# MB1066.net
KiCad netlist of a schematic drawn in Altium Designer
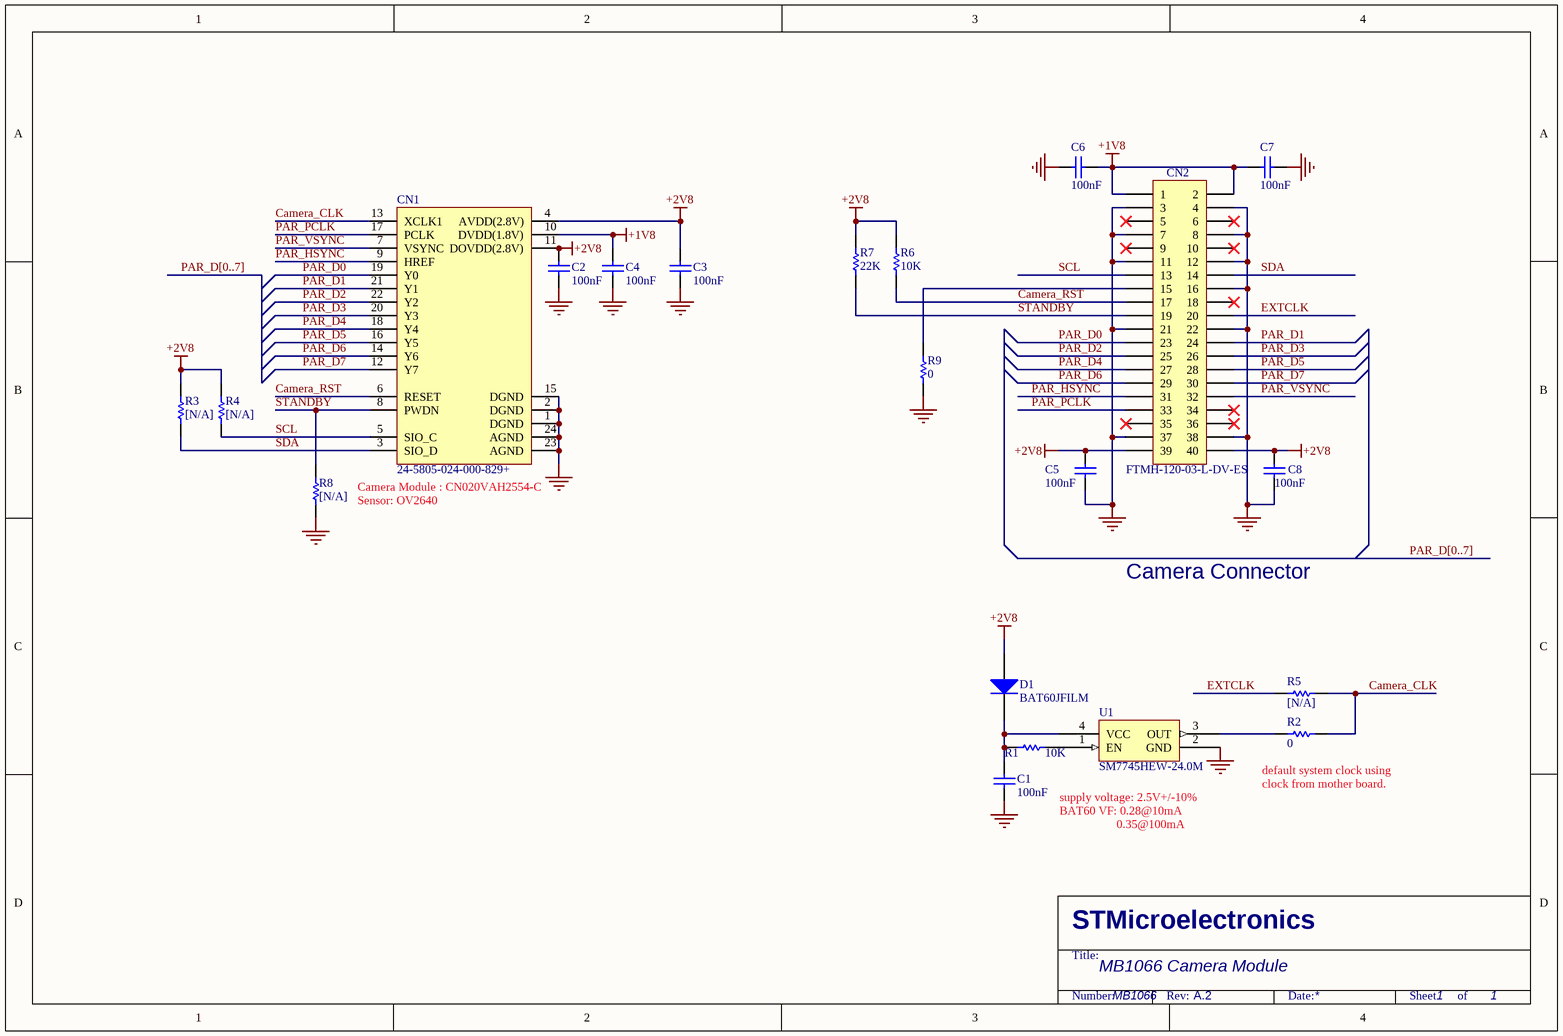
[diagram p0: MB1066.SchDoc]

(export (version "E")
  (design (tool "Eeschema 10.0.6"))
  (components
    (comp (ref "C1")
      (value "100nF")
      (footprint "0603C")
      (description "Capacitor")
      (fields (field (name "PUBLISHER") "Altium Limited"))
      (libsource (lib "Miscellaneous Devices") (part "Cap"))
    )
    (comp (ref "C2")
      (value "100nF")
      (footprint "0603C")
      (description "Capacitor")
      (fields (field (name "PUBLISHER") "Altium Limited"))
      (libsource (lib "Miscellaneous Devices") (part "Cap"))
    )
    (comp (ref "C3")
      (value "100nF")
      (footprint "0603L")
      (description "Capacitor")
      (fields (field (name "PUBLISHER") "Altium Limited"))
      (libsource (lib "Miscellaneous Devices") (part "Cap"))
    )
    (comp (ref "C4")
      (value "100nF")
      (footprint "0603C")
      (description "Capacitor")
      (fields (field (name "PUBLISHER") "Altium Limited"))
      (libsource (lib "Miscellaneous Devices") (part "Cap"))
    )
    (comp (ref "C5")
      (value "100nF")
      (footprint "0603C")
      (description "Capacitor")
      (fields (field (name "PUBLISHER") "Altium Limited"))
      (libsource (lib "Miscellaneous Devices") (part "Cap"))
    )
    (comp (ref "C6")
      (value "100nF")
      (footprint "0603C")
      (description "Capacitor")
      (fields (field (name "PUBLISHER") "Altium Limited"))
      (libsource (lib "Miscellaneous Devices") (part "Cap"))
    )
    (comp (ref "C7")
      (value "100nF")
      (footprint "0603C")
      (description "Capacitor")
      (fields (field (name "PUBLISHER") "Altium Limited"))
      (libsource (lib "Miscellaneous Devices") (part "Cap"))
    )
    (comp (ref "C8")
      (value "100nF")
      (footprint "0603C")
      (description "Capacitor")
      (fields (field (name "PUBLISHER") "Altium Limited"))
      (libsource (lib "Miscellaneous Devices") (part "Cap"))
    )
    (comp (ref "CN1")
      (value "24-5805-024-000-829+")
      (footprint "24-5805-024-000-829")
      (libsource (lib "MB786") (part "24-5805-024-000-829+"))
    )
    (comp (ref "CN2")
      (value "FTMH-120-03-L-DV-ES")
      (footprint "FTMH-120-03-L-DV-ES")
      (description "20*2Pins, 1mm_SMT, male")
      (fields (field (name "PUBLISHER") "Altium Limited"))
      (libsource (lib "Miscellaneous Connectors") (part "Header 20X2"))
    )
    (comp (ref "D1")
      (value "BAT60JFILM")
      (footprint "SOD-323")
      (description "Default Diode")
      (fields (field (name "PUBLISHER") "Altium Limited"))
      (libsource (lib "Miscellaneous Devices") (part "Diode"))
    )
    (comp (ref "R1")
      (value "10K")
      (footprint "0603R")
      (description "Resistor")
      (fields (field (name "PUBLISHER") "Altium Limited"))
      (libsource (lib "Miscellaneous Devices") (part "Res1"))
    )
    (comp (ref "R2")
      (value "0")
      (footprint "0603R")
      (description "Resistor")
      (fields (field (name "PUBLISHER") "Altium Limited"))
      (libsource (lib "Miscellaneous Devices") (part "Res1"))
    )
    (comp (ref "R3")
      (value "[N/A]")
      (footprint "0603R")
      (description "Resistor 10K")
      (fields (field (name "PUBLISHER") "Altium Limited"))
      (libsource (lib "Miscellaneous Devices") (part "Res1"))
    )
    (comp (ref "R4")
      (value "[N/A]")
      (footprint "0603R")
      (description "Resistor")
      (fields (field (name "PUBLISHER") "Altium Limited"))
      (libsource (lib "Miscellaneous Devices") (part "Res1"))
    )
    (comp (ref "R5")
      (value "[N/A]")
      (footprint "0603R")
      (description "Resistor")
      (fields (field (name "PUBLISHER") "Altium Limited"))
      (libsource (lib "Miscellaneous Devices") (part "Res1"))
    )
    (comp (ref "R6")
      (value "10K")
      (footprint "0603R")
      (description "Resistor")
      (fields (field (name "PUBLISHER") "Altium Limited"))
      (libsource (lib "Miscellaneous Devices") (part "Res1"))
    )
    (comp (ref "R7")
      (value "22K")
      (footprint "0603R")
      (description "Resistor")
      (fields (field (name "PUBLISHER") "Altium Limited"))
      (libsource (lib "Miscellaneous Devices") (part "Res1"))
    )
    (comp (ref "R8")
      (value "[N/A]")
      (footprint "0603R")
      (description "Resistor")
      (fields (field (name "PUBLISHER") "Altium Limited"))
      (libsource (lib "Miscellaneous Devices") (part "Res1"))
    )
    (comp (ref "R9")
      (value "0")
      (footprint "0603R")
      (description "Resistor")
      (fields (field (name "PUBLISHER") "Altium Limited"))
      (libsource (lib "Miscellaneous Devices") (part "Res1"))
    )
    (comp (ref "U1")
      (value "SM7745HEW-24.0M")
      (footprint "XTAL_5X7")
      (libsource (lib "MB784") (part "SM7745HEV-50.0M"))
    )
  )
  (nets
    (net (code "1") (name "+1V8") (class "Default")
      (node (ref "C4") (pin "1") (pinfunction "1_1") (pintype "passive"))
      (node (ref "C6") (pin "2") (pinfunction "2_2") (pintype "passive"))
      (node (ref "C7") (pin "1") (pinfunction "1_1") (pintype "passive"))
      (node (ref "CN1") (pin "10") (pinfunction "DVDD(1.8V)_10") (pintype "passive"))
      (node (ref "CN2") (pin "1") (pinfunction "1_1") (pintype "passive"))
      (node (ref "CN2") (pin "2") (pinfunction "2_2") (pintype "passive"))
    )
    (net (code "2") (name "+2V8") (class "Default")
      (node (ref "C2") (pin "1") (pinfunction "1_1") (pintype "passive"))
      (node (ref "C3") (pin "1") (pinfunction "1_1") (pintype "passive"))
      (node (ref "C5") (pin "1") (pinfunction "1_1") (pintype "passive"))
      (node (ref "C8") (pin "1") (pinfunction "1_1") (pintype "passive"))
      (node (ref "CN1") (pin "11") (pinfunction "DOVDD(2.8V)_11") (pintype "passive"))
      (node (ref "CN1") (pin "4") (pinfunction "AVDD(2.8V)_4") (pintype "passive"))
      (node (ref "CN2") (pin "39") (pinfunction "39_39") (pintype "passive"))
      (node (ref "CN2") (pin "40") (pinfunction "40_40") (pintype "passive"))
      (node (ref "D1") (pin "1") (pinfunction "A_1") (pintype "passive"))
      (node (ref "R3") (pin "1") (pinfunction "1_1") (pintype "passive"))
      (node (ref "R4") (pin "1") (pinfunction "1_1") (pintype "passive"))
      (node (ref "R6") (pin "1") (pinfunction "1_1") (pintype "passive"))
      (node (ref "R7") (pin "1") (pinfunction "1_1") (pintype "passive"))
    )
    (net (code "3") (name "/Camera_CLK") (class "Default")
      (node (ref "CN1") (pin "13") (pinfunction "XCLK1_13") (pintype "passive"))
      (node (ref "R2") (pin "2") (pinfunction "2_2") (pintype "passive"))
      (node (ref "R5") (pin "2") (pinfunction "2_2") (pintype "passive"))
    )
    (net (code "4") (name "/Camera_RST") (class "Default")
      (node (ref "CN1") (pin "6") (pinfunction "RESET_6") (pintype "passive"))
      (node (ref "CN2") (pin "17") (pinfunction "17_17") (pintype "passive"))
      (node (ref "R6") (pin "2") (pinfunction "2_2") (pintype "passive"))
    )
    (net (code "5") (name "/EXTCLK") (class "Default")
      (node (ref "CN2") (pin "20") (pinfunction "20_20") (pintype "passive"))
      (node (ref "R5") (pin "1") (pinfunction "1_1") (pintype "passive"))
    )
    (net (code "6") (name "/PAR_D0") (class "Default")
      (node (ref "CN1") (pin "19") (pinfunction "Y0_19") (pintype "passive"))
      (node (ref "CN2") (pin "23") (pinfunction "23_23") (pintype "passive"))
    )
    (net (code "7") (name "/PAR_D1") (class "Default")
      (node (ref "CN1") (pin "21") (pinfunction "Y1_21") (pintype "passive"))
      (node (ref "CN2") (pin "24") (pinfunction "24_24") (pintype "passive"))
    )
    (net (code "8") (name "/PAR_D2") (class "Default")
      (node (ref "CN1") (pin "22") (pinfunction "Y2_22") (pintype "passive"))
      (node (ref "CN2") (pin "25") (pinfunction "25_25") (pintype "passive"))
    )
    (net (code "9") (name "/PAR_D3") (class "Default")
      (node (ref "CN1") (pin "20") (pinfunction "Y3_20") (pintype "passive"))
      (node (ref "CN2") (pin "26") (pinfunction "26_26") (pintype "passive"))
    )
    (net (code "10") (name "/PAR_D4") (class "Default")
      (node (ref "CN1") (pin "18") (pinfunction "Y4_18") (pintype "passive"))
      (node (ref "CN2") (pin "27") (pinfunction "27_27") (pintype "passive"))
    )
    (net (code "11") (name "/PAR_D5") (class "Default")
      (node (ref "CN1") (pin "16") (pinfunction "Y5_16") (pintype "passive"))
      (node (ref "CN2") (pin "28") (pinfunction "28_28") (pintype "passive"))
    )
    (net (code "12") (name "/PAR_D6") (class "Default")
      (node (ref "CN1") (pin "14") (pinfunction "Y6_14") (pintype "passive"))
      (node (ref "CN2") (pin "29") (pinfunction "29_29") (pintype "passive"))
    )
    (net (code "13") (name "/PAR_D7") (class "Default")
      (node (ref "CN1") (pin "12") (pinfunction "Y7_12") (pintype "passive"))
      (node (ref "CN2") (pin "30") (pinfunction "30_30") (pintype "passive"))
    )
    (net (code "15") (name "/PAR_HSYNC") (class "Default")
      (node (ref "CN1") (pin "9") (pinfunction "HREF_9") (pintype "passive"))
      (node (ref "CN2") (pin "31") (pinfunction "31_31") (pintype "passive"))
    )
    (net (code "16") (name "/PAR_PCLK") (class "Default")
      (node (ref "CN1") (pin "17") (pinfunction "PCLK_17") (pintype "passive"))
      (node (ref "CN2") (pin "33") (pinfunction "33_33") (pintype "passive"))
    )
    (net (code "17") (name "/PAR_VSYNC") (class "Default")
      (node (ref "CN1") (pin "7") (pinfunction "VSYNC_7") (pintype "passive"))
      (node (ref "CN2") (pin "32") (pinfunction "32_32") (pintype "passive"))
    )
    (net (code "18") (name "/SCL") (class "Default")
      (node (ref "CN1") (pin "5") (pinfunction "SIO_C_5") (pintype "passive"))
      (node (ref "CN2") (pin "13") (pinfunction "13_13") (pintype "passive"))
      (node (ref "R4") (pin "2") (pinfunction "2_2") (pintype "passive"))
    )
    (net (code "19") (name "/SDA") (class "Default")
      (node (ref "CN1") (pin "3") (pinfunction "SIO_D_3") (pintype "passive"))
      (node (ref "CN2") (pin "14") (pinfunction "14_14") (pintype "passive"))
      (node (ref "R3") (pin "2") (pinfunction "2_2") (pintype "passive"))
    )
    (net (code "20") (name "/STANDBY") (class "Default")
      (node (ref "CN1") (pin "8") (pinfunction "PWDN_8") (pintype "passive"))
      (node (ref "CN2") (pin "19") (pinfunction "19_19") (pintype "passive"))
      (node (ref "R7") (pin "2") (pinfunction "2_2") (pintype "passive"))
      (node (ref "R8") (pin "2") (pinfunction "2_2") (pintype "passive"))
    )
    (net (code "21") (name "GND") (class "Default")
      (node (ref "C1") (pin "2") (pinfunction "2_2") (pintype "passive"))
      (node (ref "C2") (pin "2") (pinfunction "2_2") (pintype "passive"))
      (node (ref "C3") (pin "2") (pinfunction "2_2") (pintype "passive"))
      (node (ref "C4") (pin "2") (pinfunction "2_2") (pintype "passive"))
      (node (ref "C5") (pin "2") (pinfunction "2_2") (pintype "passive"))
      (node (ref "C6") (pin "1") (pinfunction "1_1") (pintype "passive"))
      (node (ref "C7") (pin "2") (pinfunction "2_2") (pintype "passive"))
      (node (ref "C8") (pin "2") (pinfunction "2_2") (pintype "passive"))
      (node (ref "CN1") (pin "1") (pinfunction "DGND_1") (pintype "passive"))
      (node (ref "CN1") (pin "15") (pinfunction "DGND_15") (pintype "passive"))
      (node (ref "CN1") (pin "2") (pinfunction "DGND_2") (pintype "passive"))
      (node (ref "CN1") (pin "23") (pinfunction "AGND_23") (pintype "passive"))
      (node (ref "CN1") (pin "24") (pinfunction "AGND_24") (pintype "passive"))
      (node (ref "CN2") (pin "11") (pinfunction "11_11") (pintype "passive"))
      (node (ref "CN2") (pin "12") (pinfunction "12_12") (pintype "passive"))
      (node (ref "CN2") (pin "16") (pinfunction "16_16") (pintype "passive"))
      (node (ref "CN2") (pin "21") (pinfunction "21_21") (pintype "passive"))
      (node (ref "CN2") (pin "22") (pinfunction "22_22") (pintype "passive"))
      (node (ref "CN2") (pin "3") (pinfunction "3_3") (pintype "passive"))
      (node (ref "CN2") (pin "37") (pinfunction "37_37") (pintype "passive"))
      (node (ref "CN2") (pin "38") (pinfunction "38_38") (pintype "passive"))
      (node (ref "CN2") (pin "4") (pinfunction "4_4") (pintype "passive"))
      (node (ref "CN2") (pin "7") (pinfunction "7_7") (pintype "passive"))
      (node (ref "CN2") (pin "8") (pinfunction "8_8") (pintype "passive"))
      (node (ref "R8") (pin "1") (pinfunction "1_1") (pintype "passive"))
      (node (ref "R9") (pin "2") (pinfunction "2_2") (pintype "passive"))
      (node (ref "U1") (pin "2") (pinfunction "GND_2") (pintype "passive"))
    )
    (net (code "22") (name "Net-(CN2-Pad15)") (class "Default")
      (node (ref "CN2") (pin "15") (pinfunction "15_15") (pintype "passive"))
      (node (ref "R9") (pin "1") (pinfunction "1_1") (pintype "passive"))
    )
    (net (code "23") (name "Net-(D1-K)") (class "Default")
      (node (ref "C1") (pin "1") (pinfunction "1_1") (pintype "passive"))
      (node (ref "D1") (pin "2") (pinfunction "K_2") (pintype "passive"))
      (node (ref "R1") (pin "1") (pinfunction "1_1") (pintype "passive"))
      (node (ref "U1") (pin "4") (pinfunction "VCC_4") (pintype "passive"))
    )
    (net (code "24") (name "Net-(U1-EN)") (class "Default")
      (node (ref "R1") (pin "2") (pinfunction "2_2") (pintype "passive"))
      (node (ref "U1") (pin "1") (pinfunction "EN_1") (pintype "input"))
    )
    (net (code "25") (name "Net-(U1-OUT)") (class "Default")
      (node (ref "R2") (pin "1") (pinfunction "1_1") (pintype "passive"))
      (node (ref "U1") (pin "3") (pinfunction "OUT_3") (pintype "output"))
    )
    (net (code "26") (name "unconnected-(CN2-Pad5)") (class "Default")
      (node (ref "CN2") (pin "5") (pinfunction "5_5") (pintype "passive+no_connect"))
    )
    (net (code "27") (name "unconnected-(CN2-Pad6)") (class "Default")
      (node (ref "CN2") (pin "6") (pinfunction "6_6") (pintype "passive+no_connect"))
    )
    (net (code "28") (name "unconnected-(CN2-Pad9)") (class "Default")
      (node (ref "CN2") (pin "9") (pinfunction "9_9") (pintype "passive+no_connect"))
    )
    (net (code "29") (name "unconnected-(CN2-Pad10)") (class "Default")
      (node (ref "CN2") (pin "10") (pinfunction "10_10") (pintype "passive+no_connect"))
    )
    (net (code "30") (name "unconnected-(CN2-Pad18)") (class "Default")
      (node (ref "CN2") (pin "18") (pinfunction "18_18") (pintype "passive+no_connect"))
    )
    (net (code "31") (name "unconnected-(CN2-Pad34)") (class "Default")
      (node (ref "CN2") (pin "34") (pinfunction "34_34") (pintype "passive+no_connect"))
    )
    (net (code "32") (name "unconnected-(CN2-Pad35)") (class "Default")
      (node (ref "CN2") (pin "35") (pinfunction "35_35") (pintype "passive+no_connect"))
    )
    (net (code "33") (name "unconnected-(CN2-Pad36)") (class "Default")
      (node (ref "CN2") (pin "36") (pinfunction "36_36") (pintype "passive+no_connect"))
    )
  )
)
